# Power.net
KiCad netlist of a schematic drawn in Altium Designer
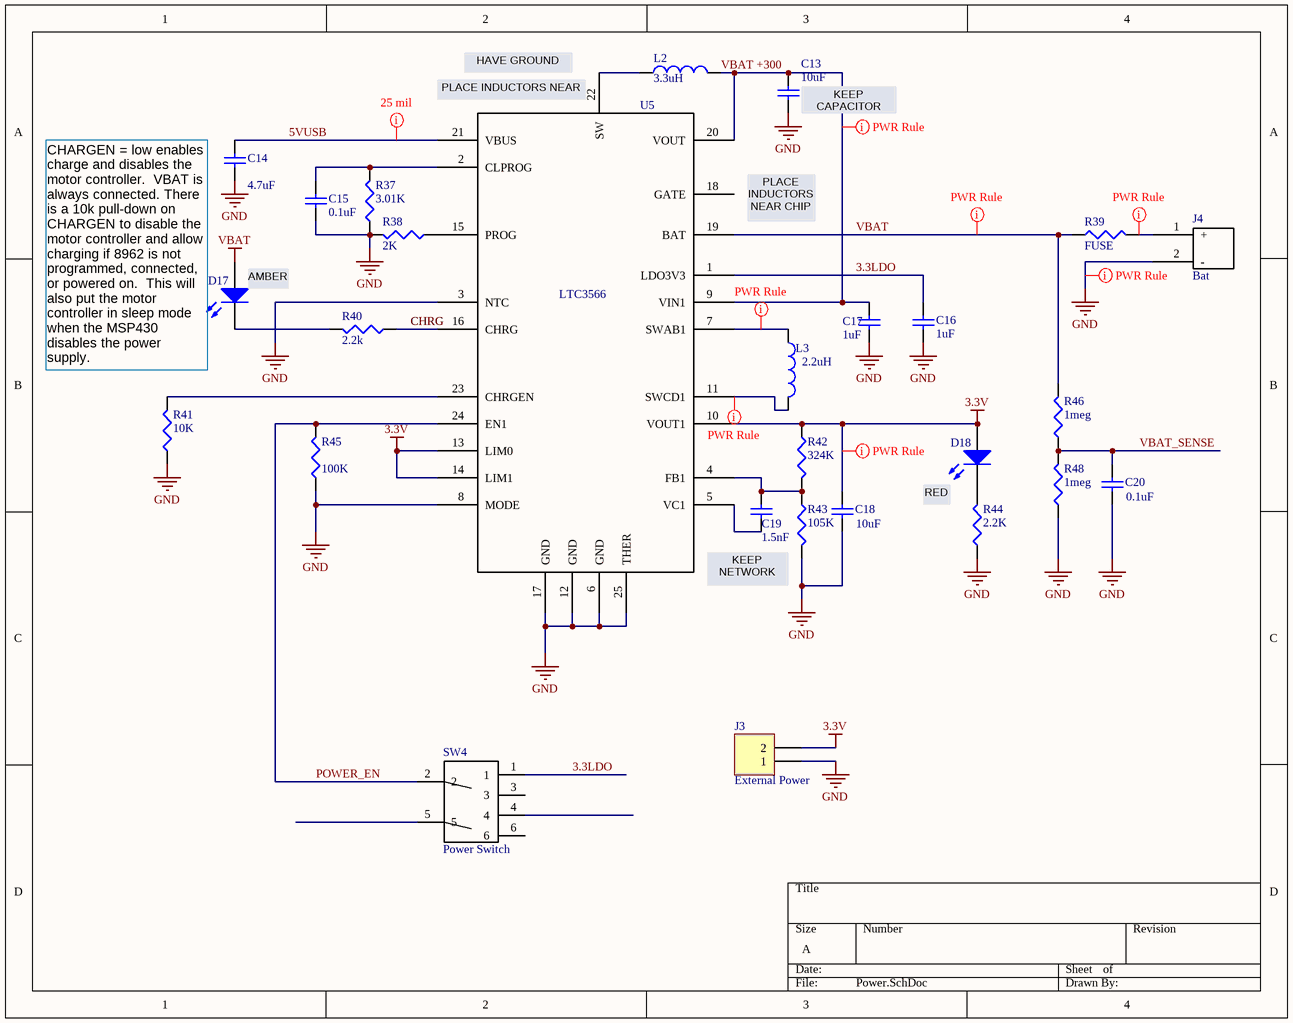
[diagram p0: Power.SchDoc]

(export (version "E")
  (design (tool "Eeschema 10.0.6"))
  (components
    (comp (ref "C13")
      (value "10uF")
      (footprint "CAPC1608L")
      (description "Capacitor")
      (fields (field (name "Comment") "Cap") (field (name "PUBLISHER") "Altium Limited"))
      (libsource (lib "Miscellaneous Devices") (part "Cap"))
    )
    (comp (ref "C14")
      (value "4.7uF")
      (footprint "CAPC1005L")
      (description "Capacitor (Semiconductor SIM Model)")
      (fields (field (name "Comment") "Cap Semi") (field (name "PUBLISHER") "Altium Limited"))
      (libsource (lib "Miscellaneous Devices") (part "Cap Semi"))
    )
    (comp (ref "C15")
      (value "0.1uF")
      (footprint "CAPC1005L")
      (description "Capacitor")
      (fields (field (name "Comment") "Cap") (field (name "PUBLISHER") "Altium Limited"))
      (libsource (lib "Miscellaneous Devices") (part "Cap"))
    )
    (comp (ref "C16")
      (value "1uF")
      (footprint "CAPC1608L")
      (description "Capacitor")
      (fields (field (name "Comment") "Cap") (field (name "PUBLISHER") "Altium Limited"))
      (libsource (lib "Miscellaneous Devices") (part "Cap"))
    )
    (comp (ref "C17")
      (value "1uF")
      (footprint "CAPC1608L")
      (description "Capacitor")
      (fields (field (name "Comment") "Cap") (field (name "PUBLISHER") "Altium Limited"))
      (libsource (lib "Miscellaneous Devices") (part "Cap"))
    )
    (comp (ref "C18")
      (value "10uF")
      (footprint "CAPC1608L")
      (description "Capacitor")
      (fields (field (name "Comment") "Cap") (field (name "PUBLISHER") "Altium Limited"))
      (libsource (lib "Miscellaneous Devices") (part "Cap"))
    )
    (comp (ref "C19")
      (value "1.5nF")
      (footprint "CAPC1005L")
      (description "Capacitor")
      (fields (field (name "Comment") "Cap") (field (name "PUBLISHER") "Altium Limited"))
      (libsource (lib "Miscellaneous Devices") (part "Cap"))
    )
    (comp (ref "C20")
      (value "0.1uF")
      (footprint "CAPC1608L")
      (description "Capacitor")
      (fields (field (name "Comment") "Cap") (field (name "PUBLISHER") "Altium Limited"))
      (libsource (lib "Miscellaneous Devices") (part "Cap"))
    )
    (comp (ref "D17")
      (value "Charge")
      (footprint "2029")
      (description "Typical RED, GREEN, YELLOW, AMBER GaAs LED")
      (fields (field (name "PUBLISHER") "Altium Limited"))
      (libsource (lib "Miscellaneous Devices") (part "LED2"))
    )
    (comp (ref "D18")
      (value "Power")
      (footprint "2029")
      (description "Typical RED, GREEN, YELLOW, AMBER GaAs LED")
      (fields (field (name "PUBLISHER") "Altium Limited"))
      (libsource (lib "Miscellaneous Devices") (part "LED2"))
    )
    (comp (ref "J3")
      (value "External Power")
      (footprint "HDR1X2")
      (description "Header, 2-Pin")
      (fields (field (name "PUBLISHER") "Altium Limited"))
      (libsource (lib "Miscellaneous Connectors") (part "Header 2"))
    )
    (comp (ref "J4")
      (value "Bat")
      (footprint "BatteryConnJST")
      (libsource (lib "mrone") (part "BatteryConnJST"))
    )
    (comp (ref "L2") (value "3.3uH") (footprint "IndPow") (libsource (lib "mrone") (part "Inductor")))
    (comp (ref "L3") (value "2.2uH") (footprint "IndPow") (libsource (lib "mrone") (part "Inductor")))
    (comp (ref "R37")
      (value "3.01K")
      (footprint "J1-0603")
      (description "Resistor")
      (fields (field (name "Comment") "Res3") (field (name "PUBLISHER") "Altium Limited"))
      (libsource (lib "Miscellaneous Devices") (part "Res3"))
    )
    (comp (ref "R38")
      (value "2K")
      (footprint "J1-0603")
      (description "Resistor")
      (fields (field (name "Comment") "Res3") (field (name "PUBLISHER") "Altium Limited"))
      (libsource (lib "Miscellaneous Devices") (part "Res3"))
    )
    (comp (ref "R39")
      (value "FUSE")
      (footprint "Miscellaneous Devices:RESC3225L")
      (description "Resistor")
      (fields (field (name "Comment") "Res3") (field (name "PUBLISHER") "Altium Limited"))
      (libsource (lib "Miscellaneous Devices") (part "Res3"))
    )
    (comp (ref "R40")
      (value "2.2k")
      (footprint "J1-0603")
      (description "Resistor")
      (fields (field (name "Comment") "Res3") (field (name "PUBLISHER") "Altium Limited"))
      (libsource (lib "Miscellaneous Devices") (part "Res3"))
    )
    (comp (ref "R41")
      (value "10K")
      (footprint "J1-0603")
      (description "Resistor")
      (fields (field (name "Comment") "Res3") (field (name "PUBLISHER") "Altium Limited"))
      (libsource (lib "Miscellaneous Devices") (part "Res3"))
    )
    (comp (ref "R42")
      (value "324K")
      (footprint "J1-0603")
      (description "Resistor")
      (fields (field (name "Comment") "Res3") (field (name "PUBLISHER") "Altium Limited"))
      (libsource (lib "Miscellaneous Devices") (part "Res3"))
    )
    (comp (ref "R43")
      (value "105K")
      (footprint "J1-0603")
      (description "Resistor")
      (fields (field (name "Comment") "Res3") (field (name "PUBLISHER") "Altium Limited"))
      (libsource (lib "Miscellaneous Devices") (part "Res3"))
    )
    (comp (ref "R44")
      (value "2.2K")
      (footprint "J1-0603")
      (description "Resistor")
      (fields (field (name "Comment") "Res3") (field (name "PUBLISHER") "Altium Limited"))
      (libsource (lib "Miscellaneous Devices") (part "Res3"))
    )
    (comp (ref "R45")
      (value "100K")
      (footprint "J1-0603")
      (description "Resistor")
      (fields (field (name "Comment") "Res3") (field (name "PUBLISHER") "Altium Limited"))
      (libsource (lib "Miscellaneous Devices") (part "Res3"))
    )
    (comp (ref "R46")
      (value "1meg")
      (footprint "J1-0603")
      (description "Resistor")
      (fields (field (name "Comment") "Res3") (field (name "PUBLISHER") "Altium Limited"))
      (libsource (lib "Miscellaneous Devices") (part "Res3"))
    )
    (comp (ref "R48")
      (value "1meg")
      (footprint "J1-0603")
      (description "Resistor")
      (fields (field (name "Comment") "Res3") (field (name "PUBLISHER") "Altium Limited"))
      (libsource (lib "Miscellaneous Devices") (part "Res3"))
    )
    (comp (ref "SW4")
      (value "Power Switch")
      (footprint "DPDTSwitch")
      (libsource (lib "mrone") (part "DPDTSwitch"))
    )
    (comp (ref "U5")
      (value "LTC3566")
      (footprint "QFN-24")
      (libsource (lib "Schematic Components") (part "LTC3566"))
    )
  )
  (nets
    (net (code "1") (name "/3.3LDO") (class "Default")
      (node (ref "C16") (pin "1") (pinfunction "1_1") (pintype "passive"))
      (node (ref "SW4") (pin "1") (pinfunction "1_1") (pintype "passive"))
      (node (ref "U5") (pin "1") (pinfunction "LDO3V3_1") (pintype "passive"))
    )
    (net (code "2") (name "/5VUSB") (class "Default")
      (node (ref "C14") (pin "2") (pinfunction "2_2") (pintype "passive"))
      (node (ref "U5") (pin "21") (pinfunction "VBUS_21") (pintype "passive"))
    )
    (net (code "3") (name "/CHRG") (class "Default")
      (node (ref "R40") (pin "1") (pinfunction "1_1") (pintype "passive"))
      (node (ref "U5") (pin "16") (pinfunction "CHRG_16") (pintype "passive"))
    )
    (net (code "4") (name "/POWER_EN") (class "Default")
      (node (ref "R45") (pin "2") (pinfunction "2_2") (pintype "passive"))
      (node (ref "SW4") (pin "2") (pinfunction "2_2") (pintype "passive"))
      (node (ref "U5") (pin "24") (pinfunction "EN1_24") (pintype "passive"))
    )
    (net (code "5") (name "/VBAT +300") (class "Default")
      (node (ref "C13") (pin "2") (pinfunction "2_2") (pintype "passive"))
      (node (ref "C17") (pin "1") (pinfunction "1_1") (pintype "passive"))
      (node (ref "L2") (pin "2") (pinfunction "2_2") (pintype "passive"))
      (node (ref "U5") (pin "20") (pinfunction "VOUT_20") (pintype "passive"))
      (node (ref "U5") (pin "9") (pinfunction "VIN1_9") (pintype "passive"))
    )
    (net (code "6") (name "/VBAT_SENSE") (class "Default")
      (node (ref "C20") (pin "2") (pinfunction "2_2") (pintype "passive"))
      (node (ref "R46") (pin "1") (pinfunction "1_1") (pintype "passive"))
      (node (ref "R48") (pin "2") (pinfunction "2_2") (pintype "passive"))
    )
    (net (code "7") (name "3.3V") (class "Default")
      (node (ref "C18") (pin "2") (pinfunction "2_2") (pintype "passive"))
      (node (ref "D18") (pin "1") (pinfunction "A_1") (pintype "passive"))
      (node (ref "J3") (pin "2") (pinfunction "2_2") (pintype "passive"))
      (node (ref "R42") (pin "1") (pinfunction "1_1") (pintype "passive"))
      (node (ref "U5") (pin "10") (pinfunction "VOUT1_10") (pintype "passive"))
      (node (ref "U5") (pin "13") (pinfunction "LIM0_13") (pintype "passive"))
      (node (ref "U5") (pin "14") (pinfunction "LIM1_14") (pintype "passive"))
    )
    (net (code "8") (name "GND") (class "Default")
      (node (ref "C13") (pin "1") (pinfunction "1_1") (pintype "passive"))
      (node (ref "C14") (pin "1") (pinfunction "1_1") (pintype "passive"))
      (node (ref "C15") (pin "1") (pinfunction "1_1") (pintype "passive"))
      (node (ref "C16") (pin "2") (pinfunction "2_2") (pintype "passive"))
      (node (ref "C17") (pin "2") (pinfunction "2_2") (pintype "passive"))
      (node (ref "C18") (pin "1") (pinfunction "1_1") (pintype "passive"))
      (node (ref "C20") (pin "1") (pinfunction "1_1") (pintype "passive"))
      (node (ref "J3") (pin "1") (pinfunction "1_1") (pintype "passive"))
      (node (ref "J4") (pin "2") (pinfunction "-_2") (pintype "passive"))
      (node (ref "R37") (pin "1") (pinfunction "1_1") (pintype "passive"))
      (node (ref "R38") (pin "2") (pinfunction "2_2") (pintype "passive"))
      (node (ref "R41") (pin "1") (pinfunction "1_1") (pintype "passive"))
      (node (ref "R43") (pin "2") (pinfunction "2_2") (pintype "passive"))
      (node (ref "R44") (pin "1") (pinfunction "1_1") (pintype "passive"))
      (node (ref "R45") (pin "1") (pinfunction "1_1") (pintype "passive"))
      (node (ref "R48") (pin "1") (pinfunction "1_1") (pintype "passive"))
      (node (ref "U5") (pin "12") (pinfunction "GND_12") (pintype "passive"))
      (node (ref "U5") (pin "17") (pinfunction "GND_17") (pintype "passive"))
      (node (ref "U5") (pin "25") (pinfunction "THER_25") (pintype "passive"))
      (node (ref "U5") (pin "3") (pinfunction "NTC_3") (pintype "passive"))
      (node (ref "U5") (pin "6") (pinfunction "GND_6") (pintype "passive"))
      (node (ref "U5") (pin "8") (pinfunction "MODE_8") (pintype "passive"))
    )
    (net (code "9") (name "Net-(D17-K)") (class "Default")
      (node (ref "D17") (pin "2") (pinfunction "K_2") (pintype "passive"))
      (node (ref "R40") (pin "2") (pinfunction "2_2") (pintype "passive"))
    )
    (net (code "10") (name "Net-(D18-K)") (class "Default")
      (node (ref "D18") (pin "2") (pinfunction "K_2") (pintype "passive"))
      (node (ref "R44") (pin "2") (pinfunction "2_2") (pintype "passive"))
    )
    (net (code "11") (name "Net-(J4-+)") (class "Default")
      (node (ref "J4") (pin "1") (pinfunction "+_1") (pintype "passive"))
      (node (ref "R39") (pin "2") (pinfunction "2_2") (pintype "passive"))
    )
    (net (code "12") (name "Net-(U5-CHRGEN)") (class "Default")
      (node (ref "R41") (pin "2") (pinfunction "2_2") (pintype "passive"))
      (node (ref "U5") (pin "23") (pinfunction "CHRGEN_23") (pintype "passive"))
    )
    (net (code "13") (name "Net-(U5-CLPROG)") (class "Default")
      (node (ref "C15") (pin "2") (pinfunction "2_2") (pintype "passive"))
      (node (ref "R37") (pin "2") (pinfunction "2_2") (pintype "passive"))
      (node (ref "U5") (pin "2") (pinfunction "CLPROG_2") (pintype "passive"))
    )
    (net (code "14") (name "Net-(U5-FB1)") (class "Default")
      (node (ref "C19") (pin "1") (pinfunction "1_1") (pintype "passive"))
      (node (ref "R42") (pin "2") (pinfunction "2_2") (pintype "passive"))
      (node (ref "R43") (pin "1") (pinfunction "1_1") (pintype "passive"))
      (node (ref "U5") (pin "4") (pinfunction "FB1_4") (pintype "passive"))
    )
    (net (code "15") (name "Net-(U5-PROG)") (class "Default")
      (node (ref "R38") (pin "1") (pinfunction "1_1") (pintype "passive"))
      (node (ref "U5") (pin "15") (pinfunction "PROG_15") (pintype "passive"))
    )
    (net (code "16") (name "Net-(U5-SW)") (class "Default")
      (node (ref "L2") (pin "1") (pinfunction "1_1") (pintype "passive"))
      (node (ref "U5") (pin "22") (pinfunction "SW_22") (pintype "passive"))
    )
    (net (code "17") (name "Net-(U5-SWAB1)") (class "Default")
      (node (ref "L3") (pin "1") (pinfunction "1_1") (pintype "passive"))
      (node (ref "U5") (pin "7") (pinfunction "SWAB1_7") (pintype "passive"))
    )
    (net (code "18") (name "Net-(U5-SWCD1)") (class "Default")
      (node (ref "L3") (pin "2") (pinfunction "2_2") (pintype "passive"))
      (node (ref "U5") (pin "11") (pinfunction "SWCD1_11") (pintype "passive"))
    )
    (net (code "19") (name "Net-(U5-VC1)") (class "Default")
      (node (ref "C19") (pin "2") (pinfunction "2_2") (pintype "passive"))
      (node (ref "U5") (pin "5") (pinfunction "VC1_5") (pintype "passive"))
    )
    (net (code "20") (name "VBAT") (class "Default")
      (node (ref "D17") (pin "1") (pinfunction "A_1") (pintype "passive"))
      (node (ref "R39") (pin "1") (pinfunction "1_1") (pintype "passive"))
      (node (ref "R46") (pin "2") (pinfunction "2_2") (pintype "passive"))
      (node (ref "U5") (pin "19") (pinfunction "BAT_19") (pintype "passive"))
    )
    (net (code "21") (name "unconnected-(SW4-Pad3)") (class "Default")
      (node (ref "SW4") (pin "3") (pinfunction "3_3") (pintype "passive"))
    )
    (net (code "22") (name "unconnected-(SW4-Pad4)") (class "Default")
      (node (ref "SW4") (pin "4") (pinfunction "4_4") (pintype "passive"))
    )
    (net (code "23") (name "unconnected-(SW4-Pad5)") (class "Default")
      (node (ref "SW4") (pin "5") (pinfunction "5_5") (pintype "passive"))
    )
    (net (code "24") (name "unconnected-(SW4-Pad6)") (class "Default")
      (node (ref "SW4") (pin "6") (pinfunction "6_6") (pintype "passive"))
    )
    (net (code "25") (name "unconnected-(U5-GATE-Pad18)") (class "Default")
      (node (ref "U5") (pin "18") (pinfunction "GATE_18") (pintype "passive"))
    )
  )
)
